# Kontrollerkort_top.net
KiCad netlist of a schematic drawn in Altium Designer
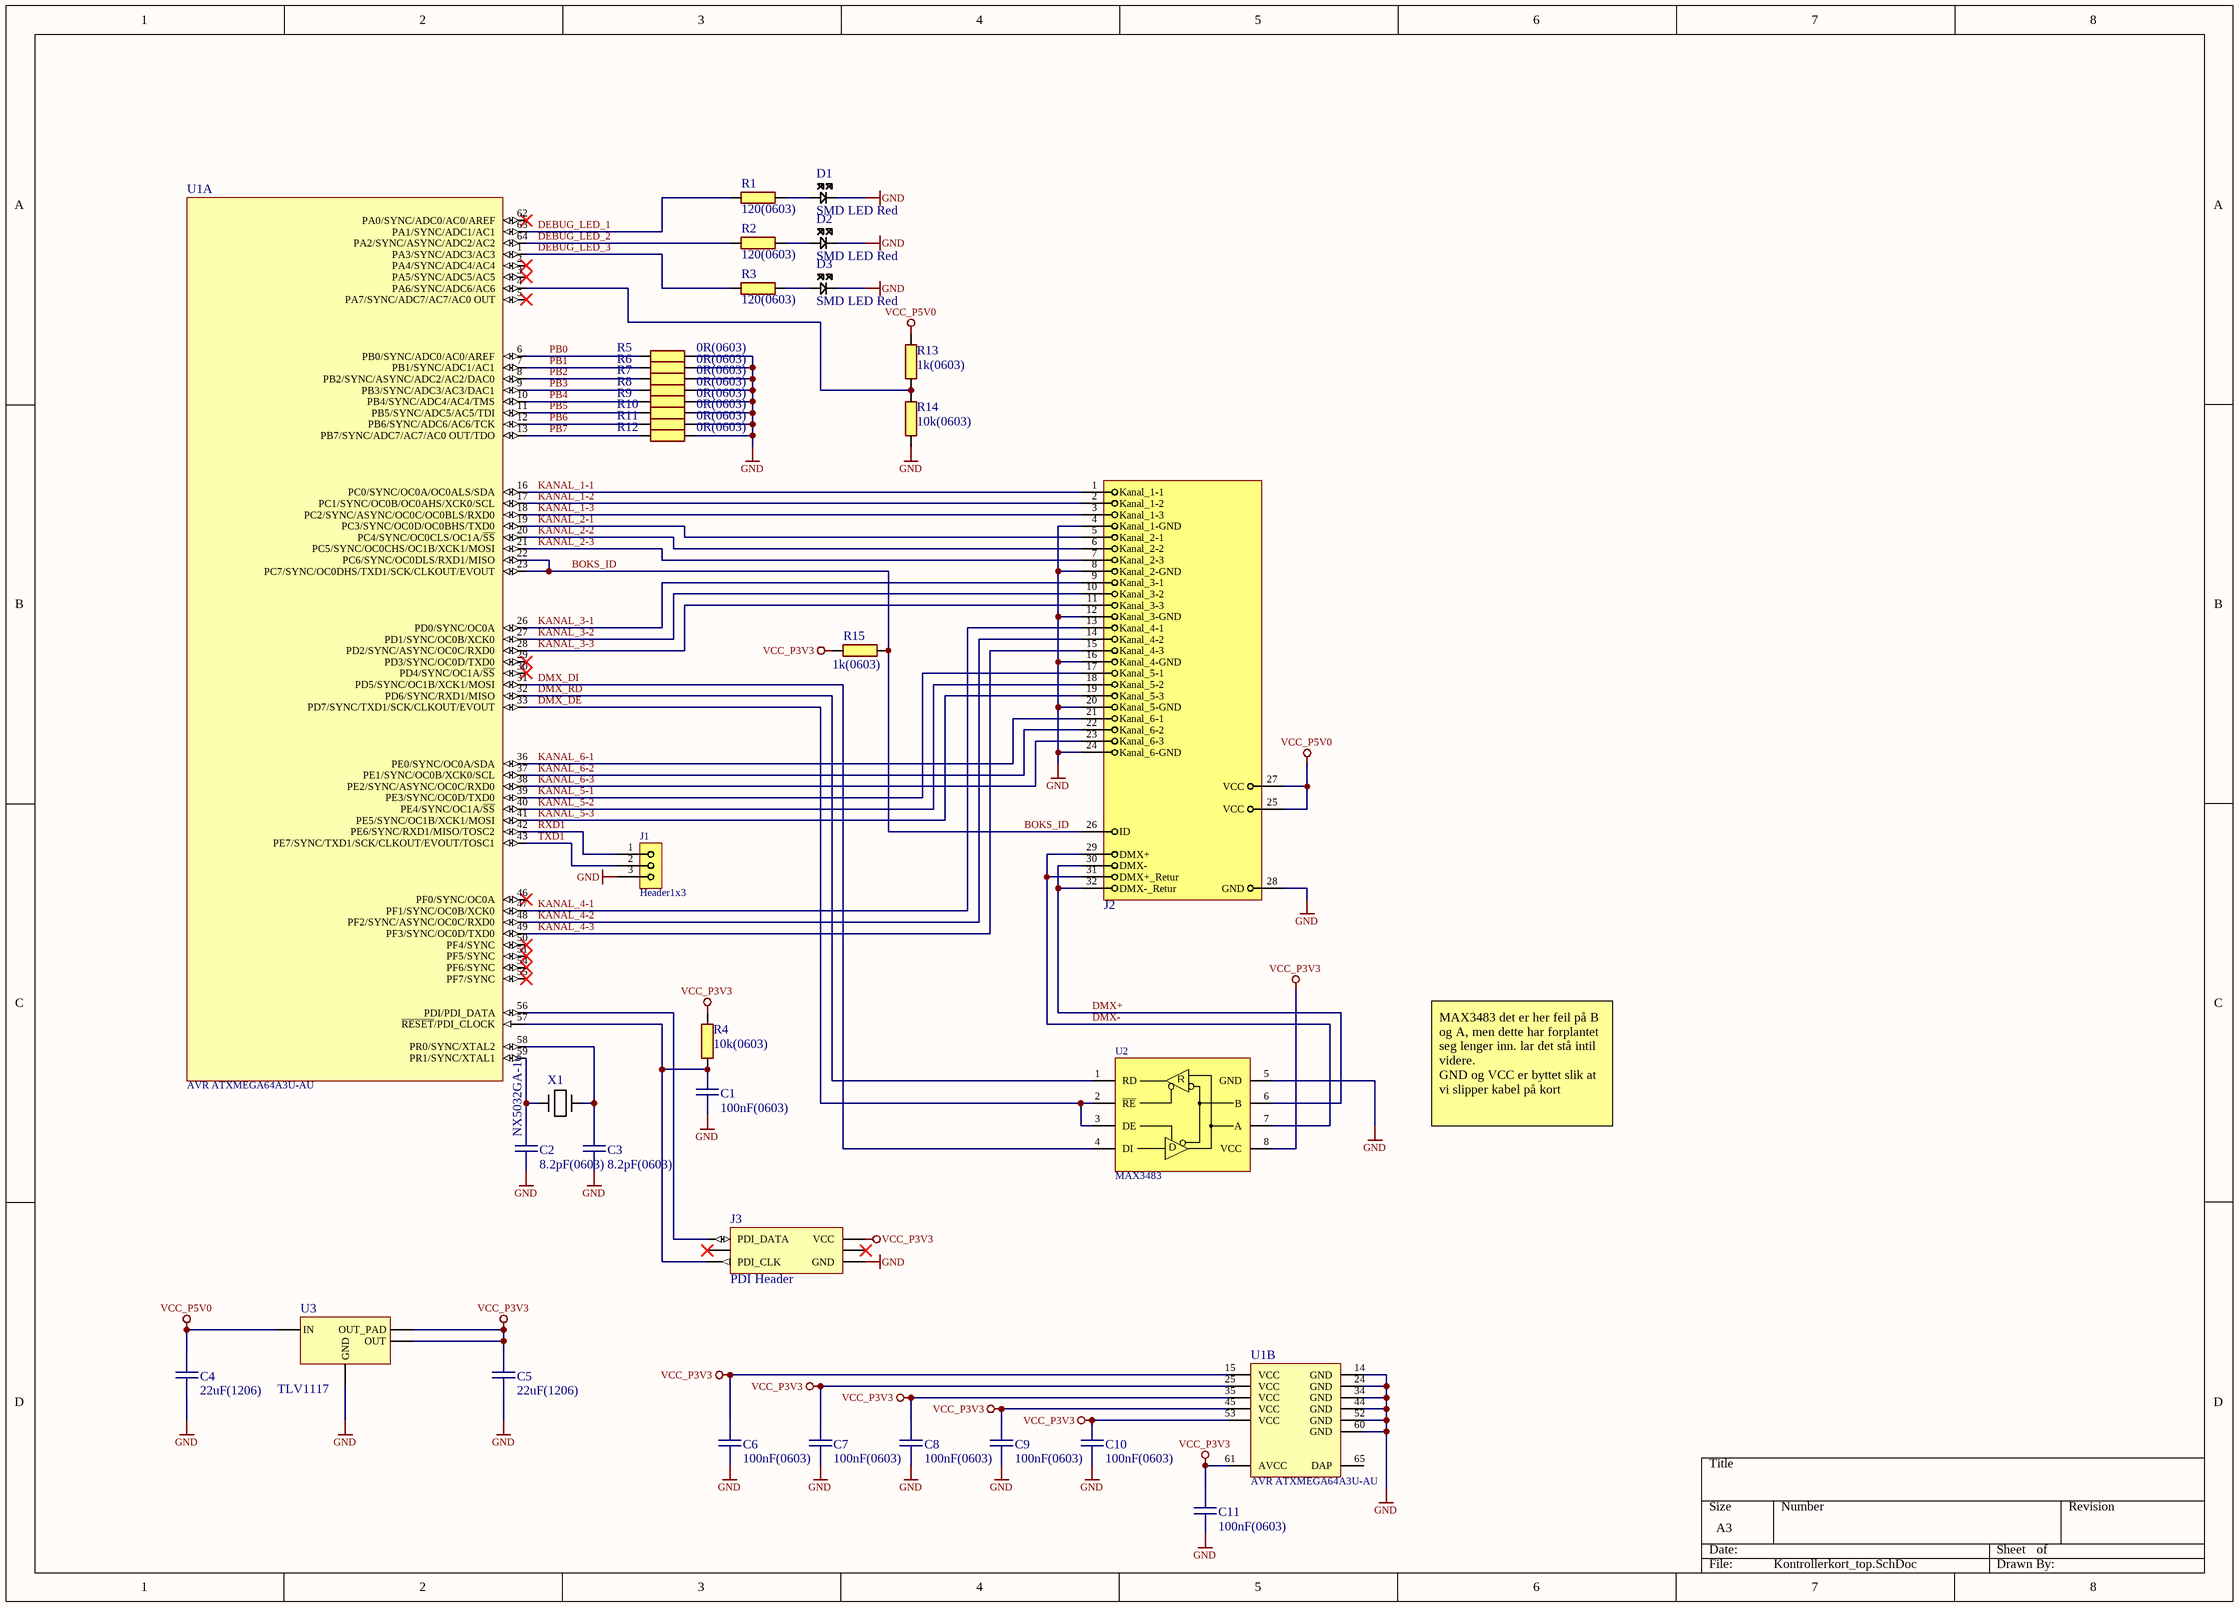
[diagram p0: Kontrollerkort_top.SchDoc]

(export (version "E")
  (design (tool "Eeschema 10.0.6"))
  (components
    (comp (ref "C1")
      (value "100nF(0603)")
      (footprint "CAPC0603(1608)55_N")
      (description "100nF 0603 5% X7R 50V")
      (libsource (lib "OVLib") (part "CAP"))
    )
    (comp (ref "C2")
      (value "8.2pF(0603)")
      (footprint "CAPC0603(1608)55_N")
      (description "0603 5% NP0 50V")
      (libsource (lib "OVLib") (part "CAP"))
    )
    (comp (ref "C3")
      (value "8.2pF(0603)")
      (footprint "CAPC0603(1608)55_N")
      (description "0603 5% NP0 50V")
      (libsource (lib "OVLib") (part "CAP"))
    )
    (comp (ref "C4")
      (value "22uF(1206)")
      (footprint "CAPC1206(3216)170_N")
      (description "1206 10% Tantalum 10V")
      (libsource (lib "OVLib") (part "CAP"))
    )
    (comp (ref "C5")
      (value "22uF(1206)")
      (footprint "CAPC1206(3216)170_N")
      (description "1206 10% Tantalum 10V")
      (libsource (lib "OVLib") (part "CAP"))
    )
    (comp (ref "C6")
      (value "100nF(0603)")
      (footprint "CAPC0603(1608)55_N")
      (description "100nF 0603 5% X7R 50V")
      (libsource (lib "OVLib") (part "CAP"))
    )
    (comp (ref "C7")
      (value "100nF(0603)")
      (footprint "CAPC0603(1608)55_N")
      (description "100nF 0603 5% X7R 50V")
      (libsource (lib "OVLib") (part "CAP"))
    )
    (comp (ref "C8")
      (value "100nF(0603)")
      (footprint "CAPC0603(1608)55_N")
      (description "100nF 0603 5% X7R 50V")
      (libsource (lib "OVLib") (part "CAP"))
    )
    (comp (ref "C9")
      (value "100nF(0603)")
      (footprint "CAPC0603(1608)55_N")
      (description "100nF 0603 5% X7R 50V")
      (libsource (lib "OVLib") (part "CAP"))
    )
    (comp (ref "C10")
      (value "100nF(0603)")
      (footprint "CAPC0603(1608)55_N")
      (description "100nF 0603 5% X7R 50V")
      (libsource (lib "OVLib") (part "CAP"))
    )
    (comp (ref "C11")
      (value "100nF(0603)")
      (footprint "CAPC0603(1608)55_N")
      (description "100nF 0603 5% X7R 50V")
      (libsource (lib "OVLib") (part "CAP"))
    )
    (comp (ref "D1")
      (value "SMD LED Red")
      (footprint "I_LEDC0603(1608)_N")
      (description "SMD")
      (libsource (lib "OVLib") (part "LED"))
    )
    (comp (ref "D2")
      (value "SMD LED Red")
      (footprint "I_LEDC0603(1608)_N")
      (description "SMD")
      (libsource (lib "OVLib") (part "LED"))
    )
    (comp (ref "D3")
      (value "SMD LED Red")
      (footprint "I_LEDC0603(1608)_N")
      (description "SMD")
      (libsource (lib "OVLib") (part "LED"))
    )
    (comp (ref "J1")
      (value "Header1x3")
      (footprint "HDRV3W64P254_1X3_762X254X900B")
      (description "2,54mm pitch")
      (libsource (lib "OVLib") (part "Header1x3"))
    )
    (comp (ref "J2")
      (value "Lysreklameparalellbusskontakt2015")
      (footprint "HDRRA32W64P254_2X16_4064X1260X600B")
      (libsource (lib "Lysreklameparalellbusskontakt2015") (part "Lysreklameparalellbusskontakt2015"))
    )
    (comp (ref "J3")
      (value "PDI Header")
      (footprint "HEADER_3x2")
      (description "PDI Xmega programming header")
      (libsource (lib "OVLib") (part "PDI-HEADER"))
    )
    (comp (ref "R1")
      (value "120(0603)")
      (footprint "RESC0603(1608)_N")
      (description "120R 0603 0.1W 1% Thick film resistor")
      (libsource (lib "") (part "Resistor2_1"))
    )
    (comp (ref "R2")
      (value "120(0603)")
      (footprint "RESC0603(1608)_N")
      (description "120R 0603 0.1W 1% Thick film resistor")
      (libsource (lib "") (part "Resistor2_1"))
    )
    (comp (ref "R3")
      (value "120(0603)")
      (footprint "RESC0603(1608)_N")
      (description "120R 0603 0.1W 1% Thick film resistor")
      (libsource (lib "") (part "Resistor2_1"))
    )
    (comp (ref "R4")
      (value "10k(0603)")
      (footprint "RESC0603(1608)_N")
      (description "10k 0603 0.1W 1% Thick film resistor")
      (libsource (lib "OVLib") (part "Resistor2"))
    )
    (comp (ref "R5")
      (value "0R(0603)")
      (footprint "RESC0603(1608)_N")
      (description "0.1W 1% Thick film resistor")
      (libsource (lib "") (part "Resistor2_1"))
    )
    (comp (ref "R6")
      (value "0R(0603)")
      (footprint "RESC0603(1608)_N")
      (description "0.1W 1% Thick film resistor")
      (libsource (lib "") (part "Resistor2_1"))
    )
    (comp (ref "R7")
      (value "0R(0603)")
      (footprint "RESC0603(1608)_N")
      (description "0.1W 1% Thick film resistor")
      (libsource (lib "") (part "Resistor2_1"))
    )
    (comp (ref "R8")
      (value "0R(0603)")
      (footprint "RESC0603(1608)_N")
      (description "0.1W 1% Thick film resistor")
      (libsource (lib "") (part "Resistor2_1"))
    )
    (comp (ref "R9")
      (value "0R(0603)")
      (footprint "RESC0603(1608)_N")
      (description "0.1W 1% Thick film resistor")
      (libsource (lib "") (part "Resistor2_1"))
    )
    (comp (ref "R10")
      (value "0R(0603)")
      (footprint "RESC0603(1608)_N")
      (description "0.1W 1% Thick film resistor")
      (libsource (lib "") (part "Resistor2_1"))
    )
    (comp (ref "R11")
      (value "0R(0603)")
      (footprint "RESC0603(1608)_N")
      (description "0.1W 1% Thick film resistor")
      (libsource (lib "") (part "Resistor2_1"))
    )
    (comp (ref "R12")
      (value "0R(0603)")
      (footprint "RESC0603(1608)_N")
      (description "0.1W 1% Thick film resistor")
      (libsource (lib "") (part "Resistor2_1"))
    )
    (comp (ref "R13")
      (value "1k(0603)")
      (footprint "RESC0603(1608)_N")
      (description "0603 0.1W 1% Thick film resistor")
      (libsource (lib "OVLib") (part "Resistor2"))
    )
    (comp (ref "R14")
      (value "10k(0603)")
      (footprint "RESC0603(1608)_N")
      (description "10k 0603 0.1W 1% Thick film resistor")
      (libsource (lib "OVLib") (part "Resistor2"))
    )
    (comp (ref "R15")
      (value "1k(0603)")
      (footprint "RESC0603(1608)_N")
      (description "0603 0.1W 1% Thick film resistor")
      (libsource (lib "") (part "Resistor2_2"))
    )
    (comp (ref "U1")
      (value "AVR ATXMEGA64A3U-AU")
      (footprint "TQFP64")
      (description "Mikrokontroller")
      (libsource (lib "OVLib") (part "ATXMEGA-64A3"))
    )
    (comp (ref "U2")
      (value "MAX3483")
      (footprint "SOIC-8-WIDE")
      (description "3.3V-Powered, 10Mbps and Slew-Rate-Limited True RS-485/RS-422 Transceivers")
      (libsource (lib "OVLib") (part "MAX3483"))
    )
    (comp (ref "U3")
      (value "TLV1117")
      (footprint "SOT230P700X180-4N")
      (description "3,3V Low dropout regulator")
      (libsource (lib "OVLib") (part "LDO_REGULATOR"))
    )
    (comp (ref "X1")
      (value "NX5032GA-16")
      (footprint "CRYSTAL-ABM7")
      (description "Crystal 16 MHz")
      (libsource (lib "OVLib") (part "GENERIC-CRYSTAL"))
    )
  )
  (nets
    (net (code "1") (name "/BOKS_ID") (class "Default")
      (node (ref "J2") (pin "26") (pinfunction "ID_26") (pintype "passive"))
      (node (ref "R15") (pin "1") (pinfunction "1_1") (pintype "passive"))
      (node (ref "U1") (pin "22") (pinfunction "PC6/SYNC/OC0DLS/RXD1/MISO_22") (pintype "bidirectional"))
      (node (ref "U1") (pin "23") (pinfunction "PC7/SYNC/OC0DHS/TXD1/SCK/CLKOUT/EVOUT_23") (pintype "bidirectional"))
    )
    (net (code "2") (name "/DEBUG_LED_1") (class "Default")
      (node (ref "R1") (pin "1") (pinfunction "1_1") (pintype "passive"))
      (node (ref "U1") (pin "63") (pinfunction "PA1/SYNC/ADC1/AC1_63") (pintype "bidirectional"))
    )
    (net (code "3") (name "/DEBUG_LED_2") (class "Default")
      (node (ref "R2") (pin "1") (pinfunction "1_1") (pintype "passive"))
      (node (ref "U1") (pin "64") (pinfunction "PA2/SYNC/ASYNC/ADC2/AC2_64") (pintype "bidirectional"))
    )
    (net (code "4") (name "/DEBUG_LED_3") (class "Default")
      (node (ref "R3") (pin "1") (pinfunction "1_1") (pintype "passive"))
      (node (ref "U1") (pin "1") (pinfunction "PA3/SYNC/ADC3/AC3_1") (pintype "bidirectional"))
    )
    (net (code "5") (name "/DMX+") (class "Default")
      (node (ref "J2") (pin "30") (pinfunction "DMX-_30") (pintype "passive"))
      (node (ref "J2") (pin "32") (pinfunction "DMX-_Retur_32") (pintype "passive"))
      (node (ref "U2") (pin "6") (pinfunction "B_6") (pintype "passive"))
    )
    (net (code "6") (name "/DMX-") (class "Default")
      (node (ref "J2") (pin "29") (pinfunction "DMX+_29") (pintype "passive"))
      (node (ref "J2") (pin "31") (pinfunction "DMX+_Retur_31") (pintype "passive"))
      (node (ref "U2") (pin "7") (pinfunction "A_7") (pintype "passive"))
    )
    (net (code "7") (name "/DMX_DE") (class "Default")
      (node (ref "U1") (pin "33") (pinfunction "PD7/SYNC/TXD1/SCK/CLKOUT/EVOUT_33") (pintype "bidirectional"))
      (node (ref "U2") (pin "2") (pinfunction "~{RE}_2") (pintype "passive"))
      (node (ref "U2") (pin "3") (pinfunction "DE_3") (pintype "passive"))
    )
    (net (code "8") (name "/DMX_DI") (class "Default")
      (node (ref "U1") (pin "31") (pinfunction "PD5/SYNC/OC1B/XCK1/MOSI_31") (pintype "bidirectional"))
      (node (ref "U2") (pin "4") (pinfunction "DI_4") (pintype "passive"))
    )
    (net (code "9") (name "/DMX_RD") (class "Default")
      (node (ref "U1") (pin "32") (pinfunction "PD6/SYNC/RXD1/MISO_32") (pintype "bidirectional"))
      (node (ref "U2") (pin "1") (pinfunction "RD_1") (pintype "passive"))
    )
    (net (code "10") (name "/KANAL_1-1") (class "Default")
      (node (ref "J2") (pin "1") (pinfunction "Kanal_1-1_1") (pintype "passive"))
      (node (ref "U1") (pin "16") (pinfunction "PC0/SYNC/OC0A/OC0ALS/SDA_16") (pintype "bidirectional"))
    )
    (net (code "11") (name "/KANAL_1-2") (class "Default")
      (node (ref "J2") (pin "2") (pinfunction "Kanal_1-2_2") (pintype "passive"))
      (node (ref "U1") (pin "17") (pinfunction "PC1/SYNC/OC0B/OC0AHS/XCK0/SCL_17") (pintype "bidirectional"))
    )
    (net (code "12") (name "/KANAL_1-3") (class "Default")
      (node (ref "J2") (pin "3") (pinfunction "Kanal_1-3_3") (pintype "passive"))
      (node (ref "U1") (pin "18") (pinfunction "PC2/SYNC/ASYNC/OC0C/OC0BLS/RXD0_18") (pintype "bidirectional"))
    )
    (net (code "13") (name "/KANAL_2-1") (class "Default")
      (node (ref "J2") (pin "5") (pinfunction "Kanal_2-1_5") (pintype "passive"))
      (node (ref "U1") (pin "19") (pinfunction "PC3/SYNC/OC0D/OC0BHS/TXD0_19") (pintype "bidirectional"))
    )
    (net (code "14") (name "/KANAL_2-2") (class "Default")
      (node (ref "J2") (pin "6") (pinfunction "Kanal_2-2_6") (pintype "passive"))
      (node (ref "U1") (pin "20") (pinfunction "PC4/SYNC/OC0CLS/OC1A/~{SS}_20") (pintype "bidirectional"))
    )
    (net (code "15") (name "/KANAL_2-3") (class "Default")
      (node (ref "J2") (pin "7") (pinfunction "Kanal_2-3_7") (pintype "passive"))
      (node (ref "U1") (pin "21") (pinfunction "PC5/SYNC/OC0CHS/OC1B/XCK1/MOSI_21") (pintype "bidirectional"))
    )
    (net (code "16") (name "/KANAL_3-1") (class "Default")
      (node (ref "J2") (pin "9") (pinfunction "Kanal_3-1_9") (pintype "passive"))
      (node (ref "U1") (pin "26") (pinfunction "PD0/SYNC/OC0A_26") (pintype "bidirectional"))
    )
    (net (code "17") (name "/KANAL_3-2") (class "Default")
      (node (ref "J2") (pin "10") (pinfunction "Kanal_3-2_10") (pintype "passive"))
      (node (ref "U1") (pin "27") (pinfunction "PD1/SYNC/OC0B/XCK0_27") (pintype "bidirectional"))
    )
    (net (code "18") (name "/KANAL_3-3") (class "Default")
      (node (ref "J2") (pin "11") (pinfunction "Kanal_3-3_11") (pintype "passive"))
      (node (ref "U1") (pin "28") (pinfunction "PD2/SYNC/ASYNC/OC0C/RXD0_28") (pintype "bidirectional"))
    )
    (net (code "19") (name "/KANAL_4-1") (class "Default")
      (node (ref "J2") (pin "13") (pinfunction "Kanal_4-1_13") (pintype "passive"))
      (node (ref "U1") (pin "47") (pinfunction "PF1/SYNC/OC0B/XCK0_47") (pintype "bidirectional"))
    )
    (net (code "20") (name "/KANAL_4-2") (class "Default")
      (node (ref "J2") (pin "14") (pinfunction "Kanal_4-2_14") (pintype "passive"))
      (node (ref "U1") (pin "48") (pinfunction "PF2/SYNC/ASYNC/OC0C/RXD0_48") (pintype "bidirectional"))
    )
    (net (code "21") (name "/KANAL_4-3") (class "Default")
      (node (ref "J2") (pin "15") (pinfunction "Kanal_4-3_15") (pintype "passive"))
      (node (ref "U1") (pin "49") (pinfunction "PF3/SYNC/OC0D/TXD0_49") (pintype "bidirectional"))
    )
    (net (code "22") (name "/KANAL_5-1") (class "Default")
      (node (ref "J2") (pin "17") (pinfunction "Kanal_5-1_17") (pintype "passive"))
      (node (ref "U1") (pin "39") (pinfunction "PE3/SYNC/OC0D/TXD0_39") (pintype "bidirectional"))
    )
    (net (code "23") (name "/KANAL_5-2") (class "Default")
      (node (ref "J2") (pin "18") (pinfunction "Kanal_5-2_18") (pintype "passive"))
      (node (ref "U1") (pin "40") (pinfunction "PE4/SYNC/OC1A/~{SS}_40") (pintype "bidirectional"))
    )
    (net (code "24") (name "/KANAL_5-3") (class "Default")
      (node (ref "J2") (pin "19") (pinfunction "Kanal_5-3_19") (pintype "passive"))
      (node (ref "U1") (pin "41") (pinfunction "PE5/SYNC/OC1B/XCK1/MOSI_41") (pintype "bidirectional"))
    )
    (net (code "25") (name "/KANAL_6-1") (class "Default")
      (node (ref "J2") (pin "21") (pinfunction "Kanal_6-1_21") (pintype "passive"))
      (node (ref "U1") (pin "36") (pinfunction "PE0/SYNC/OC0A/SDA_36") (pintype "bidirectional"))
    )
    (net (code "26") (name "/KANAL_6-2") (class "Default")
      (node (ref "J2") (pin "22") (pinfunction "Kanal_6-2_22") (pintype "passive"))
      (node (ref "U1") (pin "37") (pinfunction "PE1/SYNC/OC0B/XCK0/SCL_37") (pintype "bidirectional"))
    )
    (net (code "27") (name "/KANAL_6-3") (class "Default")
      (node (ref "J2") (pin "23") (pinfunction "Kanal_6-3_23") (pintype "passive"))
      (node (ref "U1") (pin "38") (pinfunction "PE2/SYNC/ASYNC/OC0C/RXD0_38") (pintype "bidirectional"))
    )
    (net (code "28") (name "/PB0") (class "Default")
      (node (ref "R5") (pin "1") (pinfunction "1_1") (pintype "passive"))
      (node (ref "U1") (pin "6") (pinfunction "PB0/SYNC/ADC0/AC0/AREF_6") (pintype "bidirectional"))
    )
    (net (code "29") (name "/PB1") (class "Default")
      (node (ref "R6") (pin "1") (pinfunction "1_1") (pintype "passive"))
      (node (ref "U1") (pin "7") (pinfunction "PB1/SYNC/ADC1/AC1_7") (pintype "bidirectional"))
    )
    (net (code "30") (name "/PB2") (class "Default")
      (node (ref "R7") (pin "1") (pinfunction "1_1") (pintype "passive"))
      (node (ref "U1") (pin "8") (pinfunction "PB2/SYNC/ASYNC/ADC2/AC2/DAC0_8") (pintype "bidirectional"))
    )
    (net (code "31") (name "/PB3") (class "Default")
      (node (ref "R8") (pin "1") (pinfunction "1_1") (pintype "passive"))
      (node (ref "U1") (pin "9") (pinfunction "PB3/SYNC/ADC3/AC3/DAC1_9") (pintype "bidirectional"))
    )
    (net (code "32") (name "/PB4") (class "Default")
      (node (ref "R9") (pin "1") (pinfunction "1_1") (pintype "passive"))
      (node (ref "U1") (pin "10") (pinfunction "PB4/SYNC/ADC4/AC4/TMS_10") (pintype "bidirectional"))
    )
    (net (code "33") (name "/PB5") (class "Default")
      (node (ref "R10") (pin "1") (pinfunction "1_1") (pintype "passive"))
      (node (ref "U1") (pin "11") (pinfunction "PB5/SYNC/ADC5/AC5/TDI_11") (pintype "bidirectional"))
    )
    (net (code "34") (name "/PB6") (class "Default")
      (node (ref "R11") (pin "1") (pinfunction "1_1") (pintype "passive"))
      (node (ref "U1") (pin "12") (pinfunction "PB6/SYNC/ADC6/AC6/TCK_12") (pintype "bidirectional"))
    )
    (net (code "35") (name "/PB7") (class "Default")
      (node (ref "R12") (pin "1") (pinfunction "1_1") (pintype "passive"))
      (node (ref "U1") (pin "13") (pinfunction "PB7/SYNC/ADC7/AC7/AC0_OUT/TDO_13") (pintype "bidirectional"))
    )
    (net (code "36") (name "/RXD1") (class "Default")
      (node (ref "J1") (pin "1") (pinfunction "1_1") (pintype "passive"))
      (node (ref "U1") (pin "42") (pinfunction "PE6/SYNC/RXD1/MISO/TOSC2_42") (pintype "bidirectional"))
    )
    (net (code "37") (name "/TXD1") (class "Default")
      (node (ref "J1") (pin "2") (pinfunction "2_2") (pintype "passive"))
      (node (ref "U1") (pin "43") (pinfunction "PE7/SYNC/TXD1/SCK/CLKOUT/EVOUT/TOSC1_43") (pintype "bidirectional"))
    )
    (net (code "38") (name "GND") (class "Default")
      (node (ref "C1") (pin "1") (pinfunction "1_1") (pintype "passive"))
      (node (ref "C10") (pin "1") (pinfunction "1_1") (pintype "passive"))
      (node (ref "C11") (pin "1") (pinfunction "1_1") (pintype "passive"))
      (node (ref "C2") (pin "1") (pinfunction "1_1") (pintype "passive"))
      (node (ref "C3") (pin "1") (pinfunction "1_1") (pintype "passive"))
      (node (ref "C4") (pin "1") (pinfunction "1_1") (pintype "passive"))
      (node (ref "C5") (pin "1") (pinfunction "1_1") (pintype "passive"))
      (node (ref "C6") (pin "1") (pinfunction "1_1") (pintype "passive"))
      (node (ref "C7") (pin "1") (pinfunction "1_1") (pintype "passive"))
      (node (ref "C8") (pin "1") (pinfunction "1_1") (pintype "passive"))
      (node (ref "C9") (pin "1") (pinfunction "1_1") (pintype "passive"))
      (node (ref "D1") (pin "2") (pinfunction "2_2") (pintype "passive"))
      (node (ref "D2") (pin "2") (pinfunction "2_2") (pintype "passive"))
      (node (ref "D3") (pin "2") (pinfunction "2_2") (pintype "passive"))
      (node (ref "J1") (pin "3") (pinfunction "3_3") (pintype "passive"))
      (node (ref "J2") (pin "12") (pinfunction "Kanal_3-GND_12") (pintype "passive"))
      (node (ref "J2") (pin "16") (pinfunction "Kanal_4-GND_16") (pintype "passive"))
      (node (ref "J2") (pin "20") (pinfunction "Kanal_5-GND_20") (pintype "passive"))
      (node (ref "J2") (pin "24") (pinfunction "Kanal_6-GND_24") (pintype "passive"))
      (node (ref "J2") (pin "28") (pinfunction "GND_28") (pintype "passive"))
      (node (ref "J2") (pin "4") (pinfunction "Kanal_1-GND_4") (pintype "passive"))
      (node (ref "J2") (pin "8") (pinfunction "Kanal_2-GND_8") (pintype "passive"))
      (node (ref "J3") (pin "6") (pinfunction "GND_6") (pintype "power_in"))
      (node (ref "R10") (pin "2") (pinfunction "2_2") (pintype "passive"))
      (node (ref "R11") (pin "2") (pinfunction "2_2") (pintype "passive"))
      (node (ref "R12") (pin "2") (pinfunction "2_2") (pintype "passive"))
      (node (ref "R14") (pin "1") (pinfunction "1_1") (pintype "passive"))
      (node (ref "R5") (pin "2") (pinfunction "2_2") (pintype "passive"))
      (node (ref "R6") (pin "2") (pinfunction "2_2") (pintype "passive"))
      (node (ref "R7") (pin "2") (pinfunction "2_2") (pintype "passive"))
      (node (ref "R8") (pin "2") (pinfunction "2_2") (pintype "passive"))
      (node (ref "R9") (pin "2") (pinfunction "2_2") (pintype "passive"))
      (node (ref "U1") (pin "14") (pinfunction "GND_14") (pintype "power_in"))
      (node (ref "U1") (pin "24") (pinfunction "GND_24") (pintype "power_in"))
      (node (ref "U1") (pin "34") (pinfunction "GND_34") (pintype "power_in"))
      (node (ref "U1") (pin "44") (pinfunction "GND_44") (pintype "power_in"))
      (node (ref "U1") (pin "52") (pinfunction "GND_52") (pintype "power_in"))
      (node (ref "U1") (pin "60") (pinfunction "GND_60") (pintype "power_in"))
      (node (ref "U2") (pin "5") (pinfunction "GND_5") (pintype "passive"))
      (node (ref "U3") (pin "1") (pinfunction "GND_1") (pintype "power_in"))
    )
    (net (code "39") (name "Net-(D1-Pad1)") (class "Default")
      (node (ref "D1") (pin "1") (pinfunction "1_1") (pintype "passive"))
      (node (ref "R1") (pin "2") (pinfunction "2_2") (pintype "passive"))
    )
    (net (code "40") (name "Net-(D2-Pad1)") (class "Default")
      (node (ref "D2") (pin "1") (pinfunction "1_1") (pintype "passive"))
      (node (ref "R2") (pin "2") (pinfunction "2_2") (pintype "passive"))
    )
    (net (code "41") (name "Net-(D3-Pad1)") (class "Default")
      (node (ref "D3") (pin "1") (pinfunction "1_1") (pintype "passive"))
      (node (ref "R3") (pin "2") (pinfunction "2_2") (pintype "passive"))
    )
    (net (code "42") (name "Net-(J3-PDI_CLK)") (class "Default")
      (node (ref "C1") (pin "2") (pinfunction "2_2") (pintype "passive"))
      (node (ref "J3") (pin "5") (pinfunction "PDI_CLK_5") (pintype "output"))
      (node (ref "R4") (pin "1") (pinfunction "1_1") (pintype "passive"))
      (node (ref "U1") (pin "57") (pinfunction "~{RESET}/PDI_CLOCK_57") (pintype "input"))
    )
    (net (code "43") (name "Net-(J3-PDI_DATA)") (class "Default")
      (node (ref "J3") (pin "1") (pinfunction "PDI_DATA_1") (pintype "bidirectional"))
      (node (ref "U1") (pin "56") (pinfunction "PDI/PDI_DATA_56") (pintype "bidirectional"))
    )
    (net (code "44") (name "Net-(U1A-PA6{slash}SYNC{slash}ADC6{slash}AC6)") (class "Default")
      (node (ref "R13") (pin "1") (pinfunction "1_1") (pintype "passive"))
      (node (ref "R14") (pin "2") (pinfunction "2_2") (pintype "passive"))
      (node (ref "U1") (pin "4") (pinfunction "PA6/SYNC/ADC6/AC6_4") (pintype "bidirectional"))
    )
    (net (code "45") (name "Net-(U1A-PR0{slash}SYNC{slash}XTAL2)") (class "Default")
      (node (ref "C3") (pin "2") (pinfunction "2_2") (pintype "passive"))
      (node (ref "U1") (pin "58") (pinfunction "PR0/SYNC/XTAL2_58") (pintype "bidirectional"))
      (node (ref "X1") (pin "2") (pintype "passive"))
    )
    (net (code "46") (name "Net-(U1A-PR1{slash}SYNC{slash}XTAL1)") (class "Default")
      (node (ref "C2") (pin "2") (pinfunction "2_2") (pintype "passive"))
      (node (ref "U1") (pin "59") (pinfunction "PR1/SYNC/XTAL1_59") (pintype "bidirectional"))
      (node (ref "X1") (pin "1") (pintype "passive"))
    )
    (net (code "47") (name "VCC_P3V3") (class "Default")
      (node (ref "C10") (pin "2") (pinfunction "2_2") (pintype "passive"))
      (node (ref "C11") (pin "2") (pinfunction "2_2") (pintype "passive"))
      (node (ref "C5") (pin "2") (pinfunction "2_2") (pintype "passive"))
      (node (ref "C6") (pin "2") (pinfunction "2_2") (pintype "passive"))
      (node (ref "C7") (pin "2") (pinfunction "2_2") (pintype "passive"))
      (node (ref "C8") (pin "2") (pinfunction "2_2") (pintype "passive"))
      (node (ref "C9") (pin "2") (pinfunction "2_2") (pintype "passive"))
      (node (ref "J3") (pin "2") (pinfunction "VCC_2") (pintype "power_in"))
      (node (ref "R15") (pin "2") (pinfunction "2_2") (pintype "passive"))
      (node (ref "R4") (pin "2") (pinfunction "2_2") (pintype "passive"))
      (node (ref "U1") (pin "15") (pinfunction "VCC_15") (pintype "power_in"))
      (node (ref "U1") (pin "25") (pinfunction "VCC_25") (pintype "power_in"))
      (node (ref "U1") (pin "35") (pinfunction "VCC_35") (pintype "power_in"))
      (node (ref "U1") (pin "45") (pinfunction "VCC_45") (pintype "power_in"))
      (node (ref "U1") (pin "53") (pinfunction "VCC_53") (pintype "power_in"))
      (node (ref "U1") (pin "61") (pinfunction "AVCC_61") (pintype "power_in"))
      (node (ref "U2") (pin "8") (pinfunction "VCC_8") (pintype "passive"))
      (node (ref "U3") (pin "2") (pinfunction "OUT_PAD_2") (pintype "power_in"))
      (node (ref "U3") (pin "4") (pinfunction "OUT_4") (pintype "power_in"))
    )
    (net (code "48") (name "VCC_P5V0") (class "Default")
      (node (ref "C4") (pin "2") (pinfunction "2_2") (pintype "passive"))
      (node (ref "J2") (pin "25") (pinfunction "VCC_25") (pintype "passive"))
      (node (ref "J2") (pin "27") (pinfunction "VCC_27") (pintype "passive"))
      (node (ref "R13") (pin "2") (pinfunction "2_2") (pintype "passive"))
      (node (ref "U3") (pin "3") (pinfunction "IN_3") (pintype "power_in"))
    )
    (net (code "49") (name "unconnected-(J3-Pad3)") (class "Default")
      (node (ref "J3") (pin "3") (pinfunction "3_3") (pintype "passive+no_connect"))
    )
    (net (code "50") (name "unconnected-(J3-Pad4)") (class "Default")
      (node (ref "J3") (pin "4") (pinfunction "4_4") (pintype "passive+no_connect"))
    )
    (net (code "51") (name "unconnected-(U1A-PA0{slash}SYNC{slash}ADC0{slash}AC0{slash}AREF-Pad62)") (class "Default")
      (node (ref "U1") (pin "62") (pinfunction "PA0/SYNC/ADC0/AC0/AREF_62") (pintype "bidirectional+no_connect"))
    )
    (net (code "52") (name "unconnected-(U1A-PA4{slash}SYNC{slash}ADC4{slash}AC4-Pad2)") (class "Default")
      (node (ref "U1") (pin "2") (pinfunction "PA4/SYNC/ADC4/AC4_2") (pintype "bidirectional+no_connect"))
    )
    (net (code "53") (name "unconnected-(U1A-PA5{slash}SYNC{slash}ADC5{slash}AC5-Pad3)") (class "Default")
      (node (ref "U1") (pin "3") (pinfunction "PA5/SYNC/ADC5/AC5_3") (pintype "bidirectional+no_connect"))
    )
    (net (code "54") (name "unconnected-(U1A-PA7{slash}SYNC{slash}ADC7{slash}AC7{slash}AC0_OUT-Pad5)") (class "Default")
      (node (ref "U1") (pin "5") (pinfunction "PA7/SYNC/ADC7/AC7/AC0_OUT_5") (pintype "bidirectional+no_connect"))
    )
    (net (code "55") (name "unconnected-(U1A-PD3{slash}SYNC{slash}OC0D{slash}TXD0-Pad29)") (class "Default")
      (node (ref "U1") (pin "29") (pinfunction "PD3/SYNC/OC0D/TXD0_29") (pintype "bidirectional+no_connect"))
    )
    (net (code "56") (name "unconnected-(U1A-PD4{slash}SYNC{slash}OC1A{slash}~{SS}-Pad30)") (class "Default")
      (node (ref "U1") (pin "30") (pinfunction "PD4/SYNC/OC1A/~{SS}_30") (pintype "bidirectional+no_connect"))
    )
    (net (code "57") (name "unconnected-(U1A-PF0{slash}SYNC{slash}OC0A-Pad46)") (class "Default")
      (node (ref "U1") (pin "46") (pinfunction "PF0/SYNC/OC0A_46") (pintype "bidirectional+no_connect"))
    )
    (net (code "58") (name "unconnected-(U1A-PF4{slash}SYNC-Pad50)") (class "Default")
      (node (ref "U1") (pin "50") (pinfunction "PF4/SYNC_50") (pintype "bidirectional+no_connect"))
    )
    (net (code "59") (name "unconnected-(U1A-PF5{slash}SYNC-Pad51)") (class "Default")
      (node (ref "U1") (pin "51") (pinfunction "PF5/SYNC_51") (pintype "bidirectional+no_connect"))
    )
    (net (code "60") (name "unconnected-(U1A-PF6{slash}SYNC-Pad54)") (class "Default")
      (node (ref "U1") (pin "54") (pinfunction "PF6/SYNC_54") (pintype "bidirectional+no_connect"))
    )
    (net (code "61") (name "unconnected-(U1A-PF7{slash}SYNC-Pad55)") (class "Default")
      (node (ref "U1") (pin "55") (pinfunction "PF7/SYNC_55") (pintype "bidirectional+no_connect"))
    )
    (net (code "62") (name "unconnected-(U1B-DAP-Pad65)") (class "Default")
      (node (ref "U1") (pin "65") (pinfunction "DAP_65") (pintype "power_in"))
    )
  )
)
